# 6-Sensors.net
KiCad netlist of a schematic drawn in Altium Designer
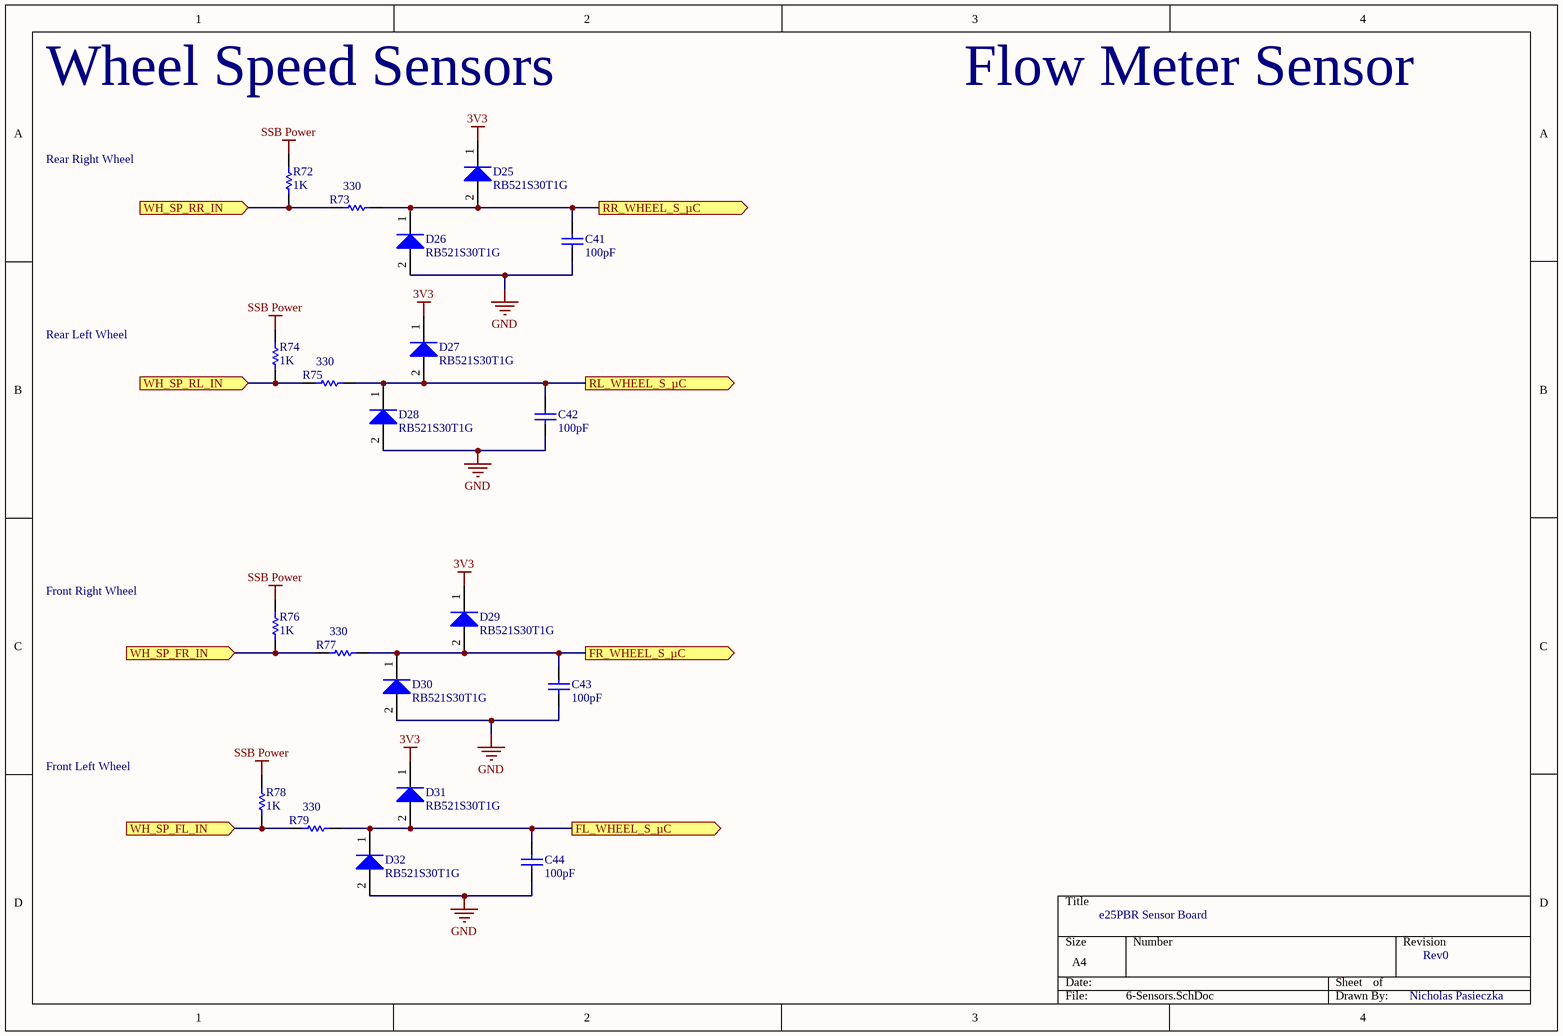
[diagram p0: 6-Sensors.SchDoc]

(export (version "E")
  (design (tool "Eeschema 10.0.6"))
  (components
    (comp (ref "C41")
      (value "100pF")
      (footprint "1608[0603]")
      (description "Capacitor")
      (fields (field (name "Comment") "Cap") (field (name "PUBLISHER") "Altium Limited"))
      (libsource (lib "Miscellaneous Devices") (part "Cap"))
    )
    (comp (ref "C42")
      (value "100pF")
      (footprint "1608[0603]")
      (description "Capacitor")
      (fields (field (name "Comment") "Cap") (field (name "PUBLISHER") "Altium Limited"))
      (libsource (lib "Miscellaneous Devices") (part "Cap"))
    )
    (comp (ref "C43")
      (value "100pF")
      (footprint "1608[0603]")
      (description "Capacitor")
      (fields (field (name "Comment") "Cap") (field (name "PUBLISHER") "Altium Limited"))
      (libsource (lib "Miscellaneous Devices") (part "Cap"))
    )
    (comp (ref "C44")
      (value "100pF")
      (footprint "1608[0603]")
      (description "Capacitor")
      (fields (field (name "Comment") "Cap") (field (name "PUBLISHER") "Altium Limited"))
      (libsource (lib "Miscellaneous Devices") (part "Cap"))
    )
    (comp (ref "D25")
      (value "RB521S30T1G")
      (footprint "ONSC-SOD-523-2-502-01_V")
      (description "Schottky Barrier Diode, 2-Pin SOD-523, Pb-Free, Tape and Reel")
      (fields (field (name "MANUFACTURER") "On Semiconductor"))
      (libsource (lib "Altium Content Vault") (part "ONSC-D-K1A2-2"))
    )
    (comp (ref "D26")
      (value "RB521S30T1G")
      (footprint "ONSC-SOD-523-2-502-01_V")
      (description "Schottky Barrier Diode, 2-Pin SOD-523, Pb-Free, Tape and Reel")
      (fields (field (name "MANUFACTURER") "On Semiconductor"))
      (libsource (lib "Altium Content Vault") (part "ONSC-D-K1A2-2"))
    )
    (comp (ref "D27")
      (value "RB521S30T1G")
      (footprint "ONSC-SOD-523-2-502-01_V")
      (description "Schottky Barrier Diode, 2-Pin SOD-523, Pb-Free, Tape and Reel")
      (fields (field (name "MANUFACTURER") "On Semiconductor"))
      (libsource (lib "Altium Content Vault") (part "ONSC-D-K1A2-2"))
    )
    (comp (ref "D28")
      (value "RB521S30T1G")
      (footprint "ONSC-SOD-523-2-502-01_V")
      (description "Schottky Barrier Diode, 2-Pin SOD-523, Pb-Free, Tape and Reel")
      (fields (field (name "MANUFACTURER") "On Semiconductor"))
      (libsource (lib "Altium Content Vault") (part "ONSC-D-K1A2-2"))
    )
    (comp (ref "D29")
      (value "RB521S30T1G")
      (footprint "ONSC-SOD-523-2-502-01_V")
      (description "Schottky Barrier Diode, 2-Pin SOD-523, Pb-Free, Tape and Reel")
      (fields (field (name "MANUFACTURER") "On Semiconductor"))
      (libsource (lib "Altium Content Vault") (part "ONSC-D-K1A2-2"))
    )
    (comp (ref "D30")
      (value "RB521S30T1G")
      (footprint "ONSC-SOD-523-2-502-01_V")
      (description "Schottky Barrier Diode, 2-Pin SOD-523, Pb-Free, Tape and Reel")
      (fields (field (name "MANUFACTURER") "On Semiconductor"))
      (libsource (lib "Altium Content Vault") (part "ONSC-D-K1A2-2"))
    )
    (comp (ref "D31")
      (value "RB521S30T1G")
      (footprint "ONSC-SOD-523-2-502-01_V")
      (description "Schottky Barrier Diode, 2-Pin SOD-523, Pb-Free, Tape and Reel")
      (fields (field (name "MANUFACTURER") "On Semiconductor"))
      (libsource (lib "Altium Content Vault") (part "ONSC-D-K1A2-2"))
    )
    (comp (ref "D32")
      (value "RB521S30T1G")
      (footprint "ONSC-SOD-523-2-502-01_V")
      (description "Schottky Barrier Diode, 2-Pin SOD-523, Pb-Free, Tape and Reel")
      (fields (field (name "MANUFACTURER") "On Semiconductor"))
      (libsource (lib "Altium Content Vault") (part "ONSC-D-K1A2-2"))
    )
    (comp (ref "R72")
      (value "1K")
      (footprint "1608[0603]")
      (description "Resistor")
      (fields (field (name "Comment") "Res1") (field (name "PUBLISHER") "Altium Limited"))
      (libsource (lib "Miscellaneous Devices") (part "Res1"))
    )
    (comp (ref "R73")
      (value "330")
      (footprint "1608[0603]")
      (description "Resistor")
      (fields (field (name "Comment") "Res1") (field (name "PUBLISHER") "Altium Limited"))
      (libsource (lib "Miscellaneous Devices") (part "Res1"))
    )
    (comp (ref "R74")
      (value "1K")
      (footprint "1608[0603]")
      (description "Resistor")
      (fields (field (name "Comment") "Res1") (field (name "PUBLISHER") "Altium Limited"))
      (libsource (lib "Miscellaneous Devices") (part "Res1"))
    )
    (comp (ref "R75")
      (value "330")
      (footprint "1608[0603]")
      (description "Resistor")
      (fields (field (name "Comment") "Res1") (field (name "PUBLISHER") "Altium Limited"))
      (libsource (lib "Miscellaneous Devices") (part "Res1"))
    )
    (comp (ref "R76")
      (value "1K")
      (footprint "1608[0603]")
      (description "Resistor")
      (fields (field (name "Comment") "Res1") (field (name "PUBLISHER") "Altium Limited"))
      (libsource (lib "Miscellaneous Devices") (part "Res1"))
    )
    (comp (ref "R77")
      (value "330")
      (footprint "1608[0603]")
      (description "Resistor")
      (fields (field (name "Comment") "Res1") (field (name "PUBLISHER") "Altium Limited"))
      (libsource (lib "Miscellaneous Devices") (part "Res1"))
    )
    (comp (ref "R78")
      (value "1K")
      (footprint "1608[0603]")
      (description "Resistor")
      (fields (field (name "Comment") "Res1") (field (name "PUBLISHER") "Altium Limited"))
      (libsource (lib "Miscellaneous Devices") (part "Res1"))
    )
    (comp (ref "R79")
      (value "330")
      (footprint "1608[0603]")
      (description "Resistor")
      (fields (field (name "Comment") "Res1") (field (name "PUBLISHER") "Altium Limited"))
      (libsource (lib "Miscellaneous Devices") (part "Res1"))
    )
  )
  (nets
    (net (code "1") (name "/FL_WHEEL_S_µC") (class "Default")
      (node (ref "C44") (pin "2") (pinfunction "2_2") (pintype "passive"))
      (node (ref "D31") (pin "2") (pinfunction "A_2") (pintype "passive"))
      (node (ref "D32") (pin "1") (pinfunction "K_1") (pintype "passive"))
      (node (ref "R79") (pin "2") (pinfunction "2_2") (pintype "passive"))
    )
    (net (code "2") (name "/FR_WHEEL_S_µC") (class "Default")
      (node (ref "C43") (pin "2") (pinfunction "2_2") (pintype "passive"))
      (node (ref "D29") (pin "2") (pinfunction "A_2") (pintype "passive"))
      (node (ref "D30") (pin "1") (pinfunction "K_1") (pintype "passive"))
      (node (ref "R77") (pin "2") (pinfunction "2_2") (pintype "passive"))
    )
    (net (code "3") (name "/RL_WHEEL_S_µC") (class "Default")
      (node (ref "C42") (pin "2") (pinfunction "2_2") (pintype "passive"))
      (node (ref "D27") (pin "2") (pinfunction "A_2") (pintype "passive"))
      (node (ref "D28") (pin "1") (pinfunction "K_1") (pintype "passive"))
      (node (ref "R75") (pin "2") (pinfunction "2_2") (pintype "passive"))
    )
    (net (code "4") (name "/RR_WHEEL_S_µC") (class "Default")
      (node (ref "C41") (pin "2") (pinfunction "2_2") (pintype "passive"))
      (node (ref "D25") (pin "2") (pinfunction "A_2") (pintype "passive"))
      (node (ref "D26") (pin "1") (pinfunction "K_1") (pintype "passive"))
      (node (ref "R73") (pin "2") (pinfunction "2_2") (pintype "passive"))
    )
    (net (code "5") (name "/WH_SP_FL_IN") (class "Default")
      (node (ref "R78") (pin "1") (pinfunction "1_1") (pintype "passive"))
      (node (ref "R79") (pin "1") (pinfunction "1_1") (pintype "passive"))
    )
    (net (code "6") (name "/WH_SP_FR_IN") (class "Default")
      (node (ref "R76") (pin "1") (pinfunction "1_1") (pintype "passive"))
      (node (ref "R77") (pin "1") (pinfunction "1_1") (pintype "passive"))
    )
    (net (code "7") (name "/WH_SP_RL_IN") (class "Default")
      (node (ref "R74") (pin "1") (pinfunction "1_1") (pintype "passive"))
      (node (ref "R75") (pin "1") (pinfunction "1_1") (pintype "passive"))
    )
    (net (code "8") (name "/WH_SP_RR_IN") (class "Default")
      (node (ref "R72") (pin "1") (pinfunction "1_1") (pintype "passive"))
      (node (ref "R73") (pin "1") (pinfunction "1_1") (pintype "passive"))
    )
    (net (code "9") (name "3V3") (class "Default")
      (node (ref "D25") (pin "1") (pinfunction "K_1") (pintype "passive"))
      (node (ref "D27") (pin "1") (pinfunction "K_1") (pintype "passive"))
      (node (ref "D29") (pin "1") (pinfunction "K_1") (pintype "passive"))
      (node (ref "D31") (pin "1") (pinfunction "K_1") (pintype "passive"))
    )
    (net (code "10") (name "GND") (class "Default")
      (node (ref "C41") (pin "1") (pinfunction "1_1") (pintype "passive"))
      (node (ref "C42") (pin "1") (pinfunction "1_1") (pintype "passive"))
      (node (ref "C43") (pin "1") (pinfunction "1_1") (pintype "passive"))
      (node (ref "C44") (pin "1") (pinfunction "1_1") (pintype "passive"))
      (node (ref "D26") (pin "2") (pinfunction "A_2") (pintype "passive"))
      (node (ref "D28") (pin "2") (pinfunction "A_2") (pintype "passive"))
      (node (ref "D30") (pin "2") (pinfunction "A_2") (pintype "passive"))
      (node (ref "D32") (pin "2") (pinfunction "A_2") (pintype "passive"))
    )
    (net (code "11") (name "SSB Power") (class "Default")
      (node (ref "R72") (pin "2") (pinfunction "2_2") (pintype "passive"))
      (node (ref "R74") (pin "2") (pinfunction "2_2") (pintype "passive"))
      (node (ref "R76") (pin "2") (pinfunction "2_2") (pintype "passive"))
      (node (ref "R78") (pin "2") (pinfunction "2_2") (pintype "passive"))
    )
  )
)
